# Optical_RX.net
KiCad netlist of a schematic drawn in Altium Designer
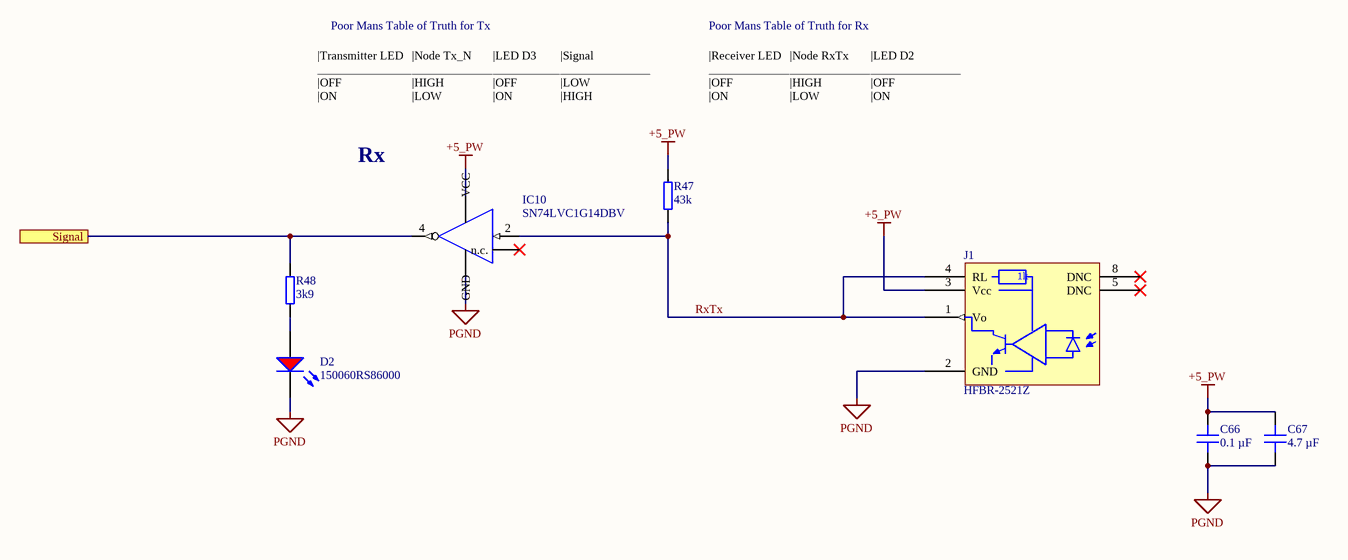
[diagram p0: Optical_RX.SchDoc]

(export (version "E")
  (design (tool "Eeschema 10.0.6"))
  (components
    (comp (ref "C66")
      (value "0.1 µF")
      (footprint "C_0603")
      (description "Capacitor 0603, 50 VDC, 0.1 µF, X7R")
      (fields
        (field (name "MANUFACTURER PART NUMBER") "C0603X104K5RAC7411")
        (field (name "MANUFACTURER") "KEMET")
        (field (name "CREATED FROM") "MGremer")
      )
      (libsource (lib "user") (part "Capacitor"))
    )
    (comp (ref "C67")
      (value "4.7 µF")
      (footprint "C_0805")
      (description "Capacitor 0805, 50 VDC, 4.7 µF, X7R")
      (fields
        (field (name "MANUFACTURER PART NUMBER") "C2012X7R1H475K125AC")
        (field (name "MANUFACTURER") "TDK")
        (field (name "CREATED FROM") "MGremer")
      )
      (libsource (lib "user") (part "Capacitor"))
    )
    (comp (ref "D2")
      (value "150060RS86000")
      (footprint "WL-SMCW_0603")
      (description "WL-SMCW SMD Mono-color Chip LED Waterclear Red")
      (fields
        (field (name "MANUFACTURER") "Wuerth Elektronik")
        (field (name "LCSC PART NUMBER") "C389517")
        (field (name "CREATED FROM") "MGremer")
      )
      (libsource (lib "user") (part "LED_Red"))
    )
    (comp (ref "IC10")
      (value "SN74LVC1G14DBV")
      (footprint "SOT23-5_L")
      (description "Inverting Schmitt trigger")
      (fields
        (field (name "MANUFACTURER") "Texas Instruments")
        (field (name "LCSC PART NUMBER") "C434069")
        (field (name "CREATED FROM") "VStarost")
      )
      (libsource (lib "user") (part "74AHCX1G14-5"))
    )
    (comp (ref "J1")
      (value "HFBR-2521Z")
      (footprint "HFBRx5XX")
      (description "Fibre Optic Receivers, LINK HORIZ 5MBd RC VR RoHS")
      (fields
        (field (name "MF") "Boadcom/Avago")
        (field (name "MANUFACTURER") "Broadcom")
        (field (name "CREATED") "2019_04_09_Kreppel")
        (field (name "CREATED FROM") "VStarost")
      )
      (libsource (lib "user") (part "HFBR-2528Z"))
    )
    (comp (ref "R47")
      (value "43k")
      (footprint "RES 0603_1608")
      (description "SMD resistor E24 series")
      (fields
        (field (name "MANUFACTURER PART NUMBER") "RK73B1JTTD433J")
        (field (name "MANUFACTURER") "KOA Speer")
        (field (name "CREATED FROM") "MGremer")
      )
      (libsource (lib "user") (part "Resistor"))
    )
    (comp (ref "R48")
      (value "3k9")
      (footprint "RES 0603_1608")
      (description "SMD resistor E24 series")
      (fields
        (field (name "MANUFACTURER PART NUMBER") "RK73B1JTTDD392J")
        (field (name "MANUFACTURER") "KOA Speer")
        (field (name "CREATED FROM") "MGremer")
      )
      (libsource (lib "user") (part "Resistor"))
    )
  )
  (nets
    (net (code "1") (name "+5_PW") (class "Default")
      (node (ref "C66") (pin "2") (pinfunction "2_2") (pintype "passive"))
      (node (ref "C67") (pin "2") (pinfunction "2_2") (pintype "passive"))
      (node (ref "IC10") (pin "5") (pinfunction "VCC_5") (pintype "power_in"))
      (node (ref "J1") (pin "3") (pinfunction "Vcc_3") (pintype "power_in"))
      (node (ref "R47") (pin "2") (pinfunction "2_2") (pintype "passive"))
    )
    (net (code "2") (name "/RxTx") (class "Default")
      (node (ref "IC10") (pin "2") (pinfunction "A_2") (pintype "input"))
      (node (ref "J1") (pin "1") (pinfunction "Vo_1") (pintype "output"))
      (node (ref "J1") (pin "4") (pinfunction "RL_4") (pintype "passive"))
      (node (ref "R47") (pin "1") (pinfunction "1_1") (pintype "passive"))
    )
    (net (code "3") (name "/Signal") (class "Default")
      (node (ref "IC10") (pin "4") (pinfunction "~{Y}_4") (pintype "output"))
      (node (ref "R48") (pin "2") (pinfunction "2_2") (pintype "passive"))
    )
    (net (code "4") (name "Net-(D2-A)") (class "Default")
      (node (ref "D2") (pin "2") (pinfunction "A_2") (pintype "passive"))
      (node (ref "R48") (pin "1") (pinfunction "1_1") (pintype "passive"))
    )
    (net (code "5") (name "PGND") (class "Default")
      (node (ref "C66") (pin "1") (pinfunction "1_1") (pintype "passive"))
      (node (ref "C67") (pin "1") (pinfunction "1_1") (pintype "passive"))
      (node (ref "D2") (pin "1") (pinfunction "K_1") (pintype "passive"))
      (node (ref "IC10") (pin "3") (pinfunction "GND_3") (pintype "power_in"))
      (node (ref "J1") (pin "2") (pinfunction "GND_2") (pintype "power_in"))
    )
    (net (code "6") (name "unconnected-(IC10-n.c.-Pad1)") (class "Default")
      (node (ref "IC10") (pin "1") (pinfunction "n.c._1") (pintype "passive+no_connect"))
    )
    (net (code "7") (name "unconnected-(J1-DNC-Pad5)") (class "Default")
      (node (ref "J1") (pin "5") (pinfunction "DNC_5") (pintype "passive+no_connect"))
    )
    (net (code "8") (name "unconnected-(J1-DNC-Pad8)") (class "Default")
      (node (ref "J1") (pin "8") (pinfunction "DNC_8") (pintype "passive+no_connect"))
    )
  )
)
